# SD_Node.net
KiCad netlist of a schematic drawn in EAGLE
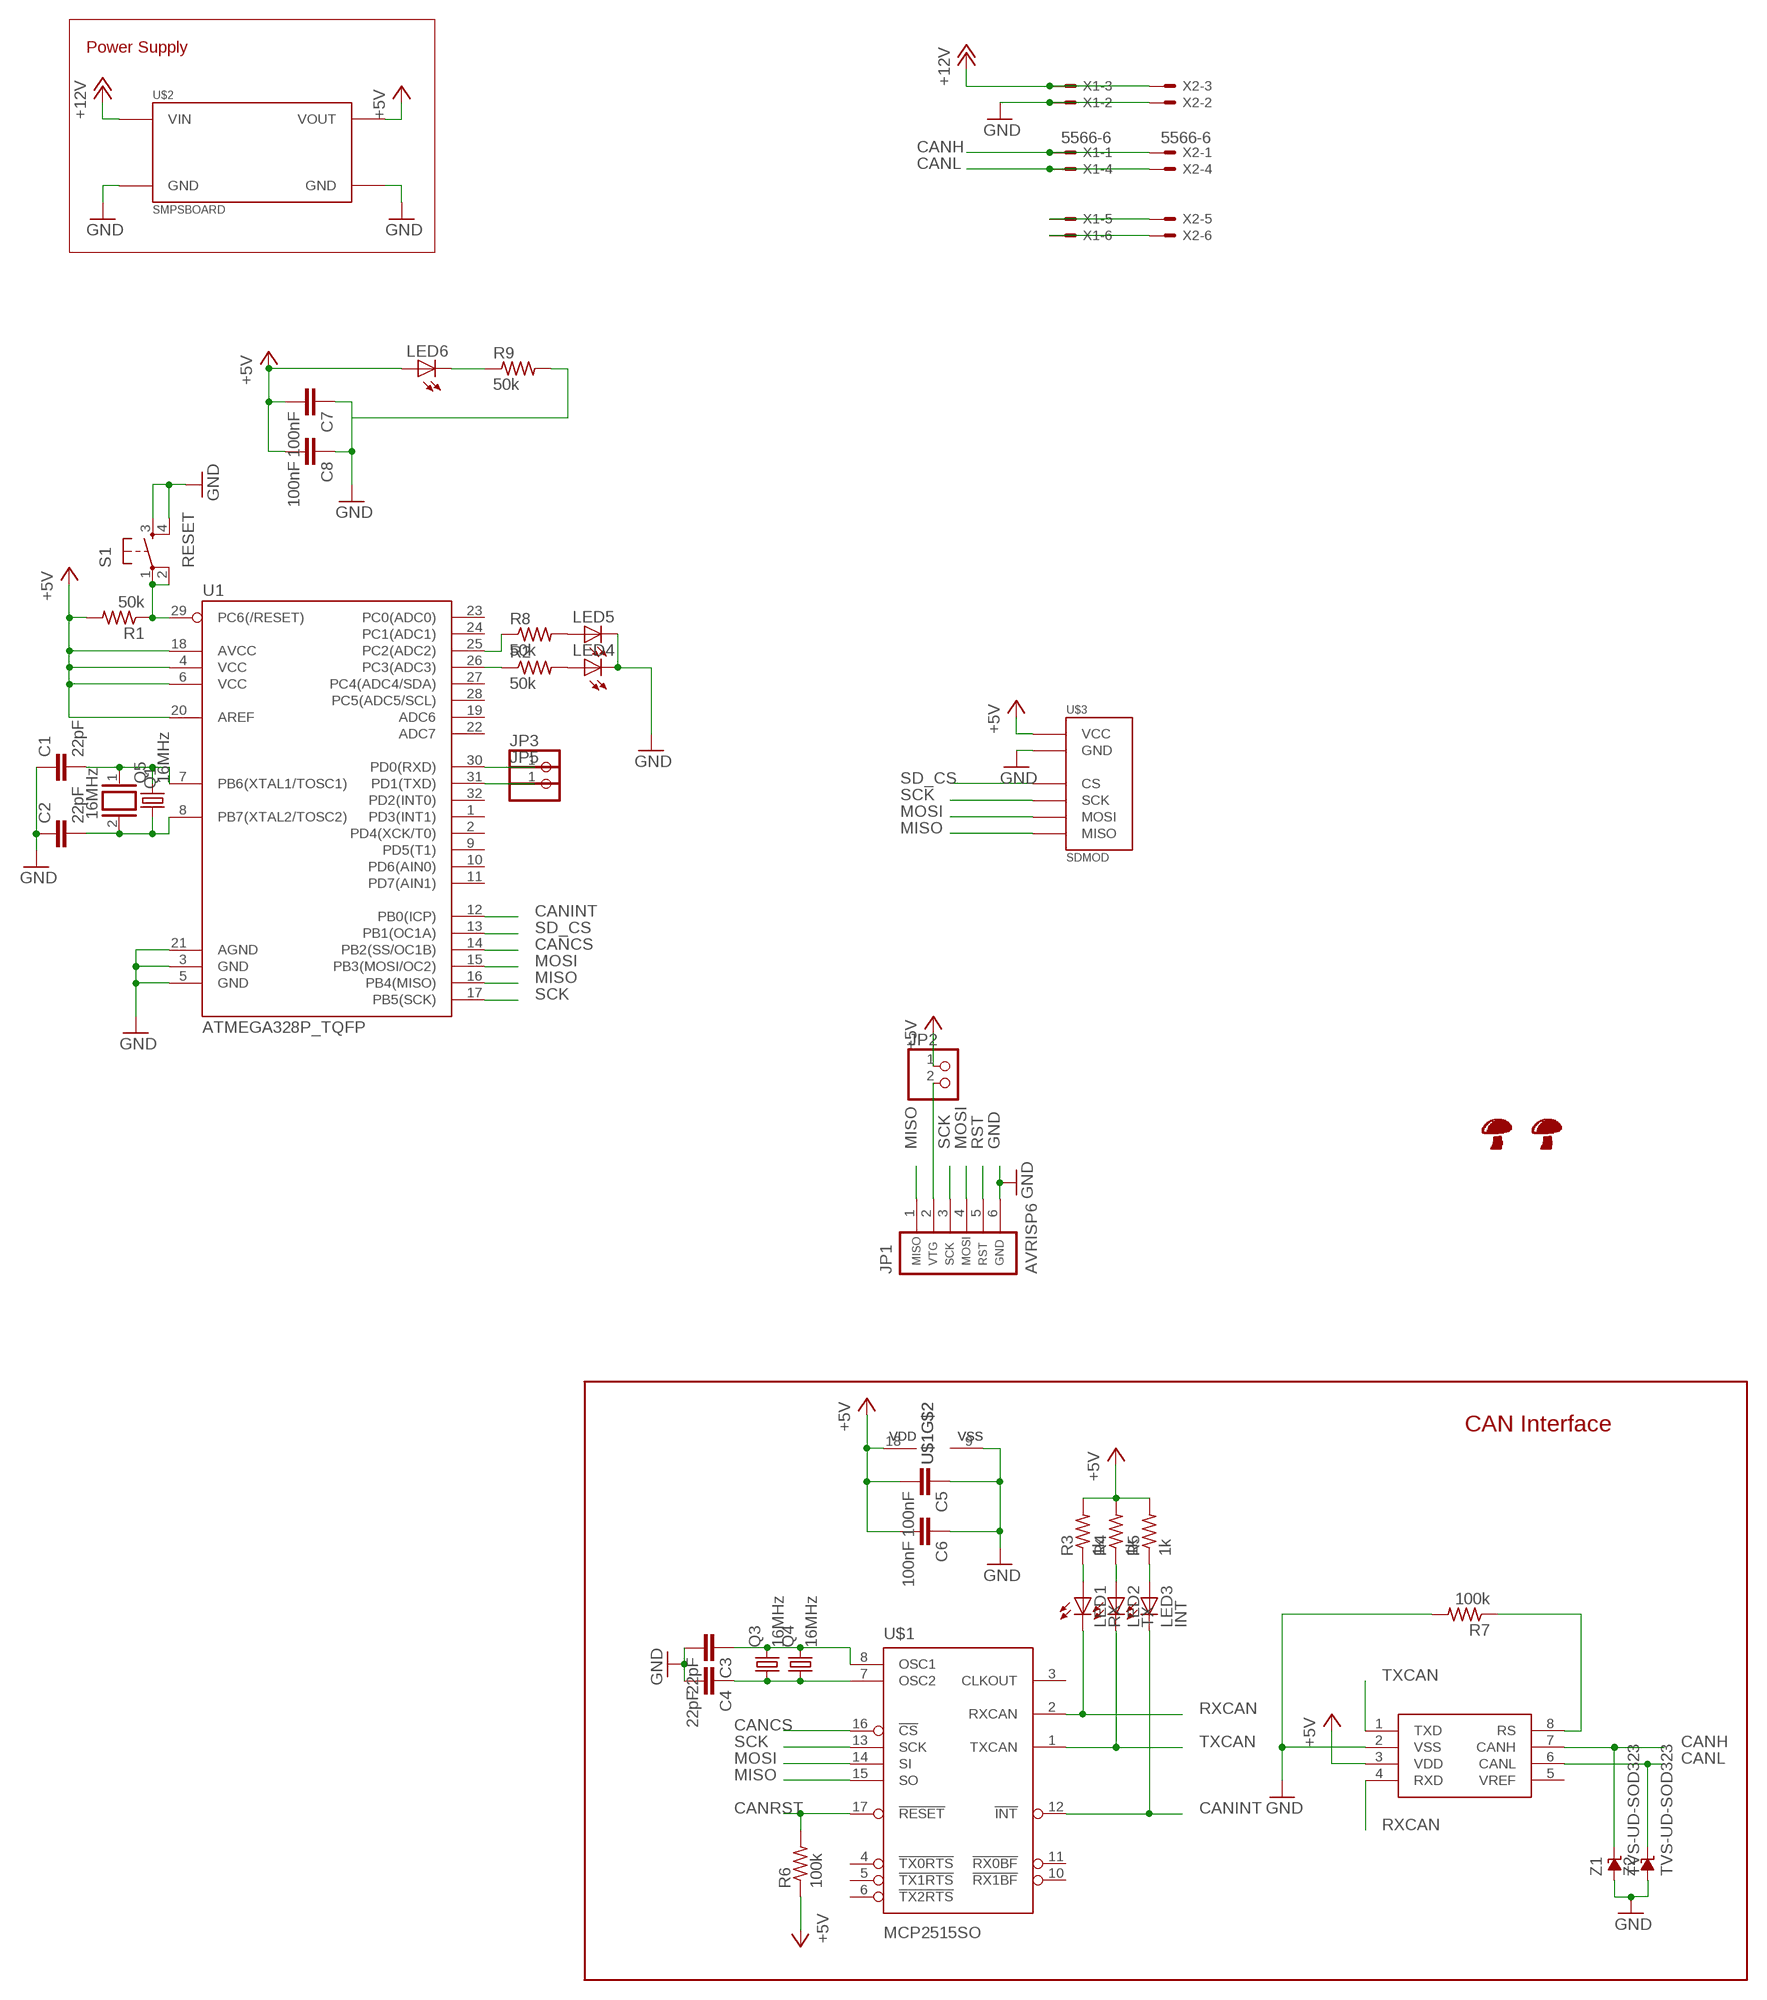
[diagram p0: schematic, sheet 1]

(export (version "E")
  (design (tool "Eeschema 10.0.6"))
  (components
    (comp (ref "C1")
      (value "22pF")
      (footprint "eagle-import:C0805")
      (libsource (lib "eagle-import") (part "C-EUC0805"))
    )
    (comp (ref "C2")
      (value "22pF")
      (footprint "eagle-import:C0805")
      (libsource (lib "eagle-import") (part "C-EUC0805"))
    )
    (comp (ref "C3")
      (value "22pF")
      (footprint "eagle-import:C0805K")
      (libsource (lib "eagle-import") (part "C-EUC0805K"))
    )
    (comp (ref "C4")
      (value "22pF")
      (footprint "eagle-import:C0805K")
      (libsource (lib "eagle-import") (part "C-EUC0805K"))
    )
    (comp (ref "C5")
      (value "100nF")
      (footprint "eagle-import:C0805K")
      (libsource (lib "eagle-import") (part "C-EUC0805K"))
    )
    (comp (ref "C6")
      (value "100nF")
      (footprint "eagle-import:C0805K")
      (libsource (lib "eagle-import") (part "C-EUC0805K"))
    )
    (comp (ref "C7")
      (value "100nF")
      (footprint "eagle-import:C0805")
      (libsource (lib "eagle-import") (part "C-EUC0805"))
    )
    (comp (ref "C8")
      (value "100nF")
      (footprint "eagle-import:C0805")
      (libsource (lib "eagle-import") (part "C-EUC0805"))
    )
    (comp (ref "JP1")
      (value "AVRISP6")
      (footprint "eagle-import:HDR-75869-131")
      (libsource (lib "eagle-import") (part "AVR-ISP6-75869-131"))
    )
    (comp (ref "JP2")
      (value "PINHD-1X2")
      (footprint "eagle-import:1X02")
      (libsource (lib "eagle-import") (part "PINHD-1X2"))
    )
    (comp (ref "JP3")
      (value "PINHD-1X1")
      (footprint "eagle-import:1X01")
      (libsource (lib "eagle-import") (part "PINHD-1X1"))
    )
    (comp (ref "JP5")
      (value "PINHD-1X1")
      (footprint "eagle-import:1X01")
      (libsource (lib "eagle-import") (part "PINHD-1X1"))
    )
    (comp (ref "LED1")
      (value "RX")
      (footprint "eagle-import:CHIP-LED0805")
      (libsource (lib "eagle-import") (part "LEDCHIP-LED0805"))
    )
    (comp (ref "LED2")
      (value "TX")
      (footprint "eagle-import:CHIP-LED0805")
      (libsource (lib "eagle-import") (part "LEDCHIP-LED0805"))
    )
    (comp (ref "LED3")
      (value "INT")
      (footprint "eagle-import:CHIP-LED0805")
      (libsource (lib "eagle-import") (part "LEDCHIP-LED0805"))
    )
    (comp (ref "LED4")
      (value "LEDCHIP-LED0805")
      (footprint "eagle-import:CHIP-LED0805")
      (libsource (lib "eagle-import") (part "LEDCHIP-LED0805"))
    )
    (comp (ref "LED5")
      (value "LEDCHIP-LED0805")
      (footprint "eagle-import:CHIP-LED0805")
      (libsource (lib "eagle-import") (part "LEDCHIP-LED0805"))
    )
    (comp (ref "LED6")
      (value "LEDCHIP-LED0805")
      (footprint "eagle-import:CHIP-LED0805")
      (libsource (lib "eagle-import") (part "LEDCHIP-LED0805"))
    )
    (comp (ref "Q1")
      (value "16MHz")
      (footprint "eagle-import:QS")
      (libsource (lib "eagle-import") (part "XTAL/S"))
    )
    (comp (ref "Q3")
      (value "16MHz")
      (footprint "eagle-import:HC49_S")
      (libsource (lib "eagle-import") (part "CRYSTALHC49S"))
    )
    (comp (ref "Q4")
      (value "16MHz")
      (footprint "eagle-import:HC49UP")
      (libsource (lib "eagle-import") (part "CRYSTALHC49UP"))
    )
    (comp (ref "Q5")
      (value "16MHz")
      (footprint "eagle-import:HC49UP")
      (libsource (lib "eagle-import") (part "CRYSTALHC49UP"))
    )
    (comp (ref "R1")
      (value "50k")
      (footprint "eagle-import:R0805")
      (libsource (lib "eagle-import") (part "R-US_R0805"))
    )
    (comp (ref "R2")
      (value "50k")
      (footprint "eagle-import:R0805")
      (libsource (lib "eagle-import") (part "R-US_R0805"))
    )
    (comp (ref "R3")
      (value "1k")
      (footprint "eagle-import:R0805")
      (libsource (lib "eagle-import") (part "R-US_R0805"))
    )
    (comp (ref "R4")
      (value "1k")
      (footprint "eagle-import:R0805")
      (libsource (lib "eagle-import") (part "R-US_R0805"))
    )
    (comp (ref "R5")
      (value "1k")
      (footprint "eagle-import:R0805")
      (libsource (lib "eagle-import") (part "R-US_R0805"))
    )
    (comp (ref "R6")
      (value "100k")
      (footprint "eagle-import:R0805")
      (libsource (lib "eagle-import") (part "R-US_R0805"))
    )
    (comp (ref "R7")
      (value "100k")
      (footprint "eagle-import:R0805")
      (libsource (lib "eagle-import") (part "R-US_R0805"))
    )
    (comp (ref "R8")
      (value "50k")
      (footprint "eagle-import:R0805")
      (libsource (lib "eagle-import") (part "R-US_R0805"))
    )
    (comp (ref "R9")
      (value "50k")
      (footprint "eagle-import:R0805")
      (libsource (lib "eagle-import") (part "R-US_R0805"))
    )
    (comp (ref "S1")
      (value "RESET")
      (footprint "eagle-import:TACTILE_SWITCH_SMD")
      (libsource (lib "eagle-import") (part "TAC_SWITCHSMD"))
    )
    (comp (ref "U$1")
      (value "MCP2515SO")
      (footprint "eagle-import:SO-18W")
      (libsource (lib "eagle-import") (part "MCP2515SO"))
    )
    (comp (ref "U$2")
      (value "SMPSBOARD")
      (footprint "eagle-import:SMPSBOARD")
      (libsource (lib "eagle-import") (part "SMPSBOARD"))
    )
    (comp (ref "U$3")
      (value "SDMOD")
      (footprint "eagle-import:SDMOD")
      (libsource (lib "eagle-import") (part "SDMOD"))
    )
    (comp (ref "U$4")
      (value "SHROOM15MM")
      (footprint "eagle-import:SHROOM15MM")
      (libsource (lib "eagle-import") (part "SHROOM15MM"))
    )
    (comp (ref "U$5")
      (value "SHROOM5MM")
      (footprint "eagle-import:SHROOM")
      (libsource (lib "eagle-import") (part "SHROOM5MM"))
    )
    (comp (ref "U1")
      (value "ATMEGA328P_TQFP")
      (footprint "eagle-import:TQFP32-08")
      (libsource (lib "eagle-import") (part "ATMEGA328P_TQFP"))
    )
    (comp (ref "U2")
      (value "MCP2551")
      (footprint "eagle-import:SO08")
      (libsource (lib "eagle-import") (part "MCP2551"))
    )
    (comp (ref "X1")
      (value "5566-6")
      (footprint "eagle-import:5566-6")
      (fields (field (name "MPN") "95566-61002"))
      (libsource (lib "eagle-import") (part "5566-6"))
    )
    (comp (ref "X2")
      (value "5566-6")
      (footprint "eagle-import:5566-6")
      (fields (field (name "MPN") "95566-61002"))
      (libsource (lib "eagle-import") (part "5566-6"))
    )
    (comp (ref "Z1")
      (value "TVS-UD-SOD323")
      (footprint "eagle-import:SOD323")
      (libsource (lib "eagle-import") (part "TVS-UD-SOD323"))
    )
    (comp (ref "Z2")
      (value "TVS-UD-SOD323")
      (footprint "eagle-import:SOD323")
      (libsource (lib "eagle-import") (part "TVS-UD-SOD323"))
    )
  )
  (nets
    (net (code "1") (name "+5V") (class "Default")
      (node (ref "C5") (pin "2") (pinfunction "2_2") (pintype "passive"))
      (node (ref "C6") (pin "2") (pinfunction "2_2") (pintype "passive"))
      (node (ref "C7") (pin "2") (pinfunction "2_2") (pintype "passive"))
      (node (ref "C8") (pin "2") (pinfunction "2_2") (pintype "passive"))
      (node (ref "JP2") (pin "1") (pinfunction "1_1") (pintype "passive"))
      (node (ref "LED6") (pin "A") (pinfunction "A_A") (pintype "passive"))
      (node (ref "R1") (pin "2") (pinfunction "2_2") (pintype "passive"))
      (node (ref "R3") (pin "2") (pinfunction "2_2") (pintype "passive"))
      (node (ref "R4") (pin "2") (pinfunction "2_2") (pintype "passive"))
      (node (ref "R5") (pin "2") (pinfunction "2_2") (pintype "passive"))
      (node (ref "R6") (pin "1") (pinfunction "1_1") (pintype "passive"))
      (node (ref "U$1") (pin "18") (pinfunction "VDD_18") (pintype "power_in"))
      (node (ref "U$2") (pin "VOUT") (pinfunction "VOUT_VOUT") (pintype "bidirectional"))
      (node (ref "U$3") (pin "VCC") (pinfunction "VCC_VCC") (pintype "bidirectional"))
      (node (ref "U1") (pin "18") (pinfunction "AVCC_18") (pintype "bidirectional"))
      (node (ref "U1") (pin "20") (pinfunction "AREF_20") (pintype "bidirectional"))
      (node (ref "U1") (pin "4") (pinfunction "VCC_4") (pintype "bidirectional"))
      (node (ref "U1") (pin "6") (pinfunction "VCC_6") (pintype "bidirectional"))
      (node (ref "U2") (pin "3") (pinfunction "VDD_3") (pintype "bidirectional"))
    )
    (net (code "2") (name "+12V") (class "Default")
      (node (ref "U$2") (pin "VIN") (pinfunction "VIN_VIN") (pintype "bidirectional"))
      (node (ref "X1") (pin "3") (pinfunction "S_3") (pintype "passive"))
      (node (ref "X2") (pin "3") (pinfunction "S_3") (pintype "passive"))
    )
    (net (code "3") (name "/CANCS") (class "Default")
      (node (ref "U$1") (pin "16") (pinfunction "~{CS}_16") (pintype "input"))
      (node (ref "U1") (pin "14") (pinfunction "PB2(SS/OC1B)_14") (pintype "bidirectional"))
    )
    (net (code "4") (name "/CANH") (class "Default")
      (node (ref "U2") (pin "7") (pinfunction "CANH_7") (pintype "bidirectional"))
      (node (ref "X1") (pin "1") (pinfunction "S_1") (pintype "passive"))
      (node (ref "X2") (pin "1") (pinfunction "S_1") (pintype "passive"))
      (node (ref "Z1") (pin "C") (pinfunction "C_C") (pintype "passive"))
    )
    (net (code "5") (name "/CANINT") (class "Default")
      (node (ref "LED3") (pin "C") (pinfunction "C_C") (pintype "passive"))
      (node (ref "U$1") (pin "12") (pinfunction "~{INT}_12") (pintype "output"))
      (node (ref "U1") (pin "12") (pinfunction "PB0(ICP)_12") (pintype "bidirectional"))
    )
    (net (code "6") (name "/CANL") (class "Default")
      (node (ref "U2") (pin "6") (pinfunction "CANL_6") (pintype "bidirectional"))
      (node (ref "X1") (pin "4") (pinfunction "S_4") (pintype "passive"))
      (node (ref "X2") (pin "4") (pinfunction "S_4") (pintype "passive"))
      (node (ref "Z2") (pin "C") (pinfunction "C_C") (pintype "passive"))
    )
    (net (code "7") (name "/CANRST") (class "Default")
      (node (ref "R6") (pin "2") (pinfunction "2_2") (pintype "passive"))
      (node (ref "U$1") (pin "17") (pinfunction "~{RESET}_17") (pintype "input"))
    )
    (net (code "8") (name "/MISO") (class "Default")
      (node (ref "JP1") (pin "1") (pinfunction "1_1") (pintype "passive"))
      (node (ref "U$1") (pin "15") (pinfunction "SO_15") (pintype "output"))
      (node (ref "U$3") (pin "MISO") (pinfunction "MISO_MISO") (pintype "bidirectional"))
      (node (ref "U1") (pin "16") (pinfunction "PB4(MISO)_16") (pintype "bidirectional"))
    )
    (net (code "9") (name "/MOSI") (class "Default")
      (node (ref "JP1") (pin "4") (pinfunction "4_4") (pintype "passive"))
      (node (ref "U$1") (pin "14") (pinfunction "SI_14") (pintype "input"))
      (node (ref "U$3") (pin "MOSI") (pinfunction "MOSI_MOSI") (pintype "bidirectional"))
      (node (ref "U1") (pin "15") (pinfunction "PB3(MOSI/OC2)_15") (pintype "bidirectional"))
    )
    (net (code "10") (name "/RST") (class "Default")
      (node (ref "JP1") (pin "5") (pinfunction "5_5") (pintype "passive"))
      (node (ref "R1") (pin "1") (pinfunction "1_1") (pintype "passive"))
      (node (ref "S1") (pin "1") (pinfunction "1_1") (pintype "passive"))
      (node (ref "S1") (pin "2") (pinfunction "2_2") (pintype "passive"))
      (node (ref "U1") (pin "29") (pinfunction "PC6(/RESET)_29") (pintype "bidirectional"))
    )
    (net (code "11") (name "/RXCAN") (class "Default")
      (node (ref "LED1") (pin "C") (pinfunction "C_C") (pintype "passive"))
      (node (ref "U$1") (pin "2") (pinfunction "RXCAN_2") (pintype "input"))
      (node (ref "U2") (pin "4") (pinfunction "RXD_4") (pintype "bidirectional"))
    )
    (net (code "12") (name "/SCK") (class "Default")
      (node (ref "JP1") (pin "3") (pinfunction "3_3") (pintype "passive"))
      (node (ref "U$1") (pin "13") (pinfunction "SCK_13") (pintype "input"))
      (node (ref "U$3") (pin "SCK") (pinfunction "SCK_SCK") (pintype "bidirectional"))
      (node (ref "U1") (pin "17") (pinfunction "PB5(SCK)_17") (pintype "bidirectional"))
    )
    (net (code "13") (name "/SD_CS") (class "Default")
      (node (ref "U$3") (pin "CS") (pinfunction "CS_CS") (pintype "bidirectional"))
      (node (ref "U1") (pin "13") (pinfunction "PB1(OC1A)_13") (pintype "bidirectional"))
    )
    (net (code "14") (name "/TXCAN") (class "Default")
      (node (ref "LED2") (pin "C") (pinfunction "C_C") (pintype "passive"))
      (node (ref "U$1") (pin "1") (pinfunction "TXCAN_1") (pintype "output"))
      (node (ref "U2") (pin "1") (pinfunction "TXD_1") (pintype "bidirectional"))
    )
    (net (code "15") (name "GND") (class "Default")
      (node (ref "C1") (pin "1") (pinfunction "1_1") (pintype "passive"))
      (node (ref "C2") (pin "1") (pinfunction "1_1") (pintype "passive"))
      (node (ref "C3") (pin "2") (pinfunction "2_2") (pintype "passive"))
      (node (ref "C4") (pin "2") (pinfunction "2_2") (pintype "passive"))
      (node (ref "C5") (pin "1") (pinfunction "1_1") (pintype "passive"))
      (node (ref "C6") (pin "1") (pinfunction "1_1") (pintype "passive"))
      (node (ref "C7") (pin "1") (pinfunction "1_1") (pintype "passive"))
      (node (ref "C8") (pin "1") (pinfunction "1_1") (pintype "passive"))
      (node (ref "JP1") (pin "6") (pinfunction "6_6") (pintype "passive"))
      (node (ref "LED4") (pin "C") (pinfunction "C_C") (pintype "passive"))
      (node (ref "LED5") (pin "C") (pinfunction "C_C") (pintype "passive"))
      (node (ref "R7") (pin "2") (pinfunction "2_2") (pintype "passive"))
      (node (ref "R9") (pin "2") (pinfunction "2_2") (pintype "passive"))
      (node (ref "S1") (pin "3") (pinfunction "3_3") (pintype "passive"))
      (node (ref "S1") (pin "4") (pinfunction "4_4") (pintype "passive"))
      (node (ref "U$1") (pin "9") (pinfunction "VSS_9") (pintype "power_in"))
      (node (ref "U$2") (pin "GND") (pinfunction "GND_GND") (pintype "bidirectional"))
      (node (ref "U$2") (pin "GND@") (pinfunction "GND_GND@") (pintype "bidirectional"))
      (node (ref "U$3") (pin "GND") (pinfunction "GND_GND") (pintype "bidirectional"))
      (node (ref "U1") (pin "21") (pinfunction "AGND_21") (pintype "bidirectional"))
      (node (ref "U1") (pin "3") (pinfunction "GND_3") (pintype "bidirectional"))
      (node (ref "U1") (pin "5") (pinfunction "GND_5") (pintype "bidirectional"))
      (node (ref "U2") (pin "2") (pinfunction "VSS_2") (pintype "bidirectional"))
      (node (ref "X1") (pin "2") (pinfunction "S_2") (pintype "passive"))
      (node (ref "X2") (pin "2") (pinfunction "S_2") (pintype "passive"))
      (node (ref "Z1") (pin "A") (pinfunction "A_A") (pintype "passive"))
      (node (ref "Z2") (pin "A") (pinfunction "A_A") (pintype "passive"))
    )
    (net (code "16") (name "Net-(JP1-Pad2)") (class "Default")
      (node (ref "JP1") (pin "2") (pinfunction "2_2") (pintype "passive"))
      (node (ref "JP2") (pin "2") (pinfunction "2_2") (pintype "passive"))
    )
    (net (code "17") (name "Net-(LED1-PadA)") (class "Default")
      (node (ref "LED1") (pin "A") (pinfunction "A_A") (pintype "passive"))
      (node (ref "R3") (pin "1") (pinfunction "1_1") (pintype "passive"))
    )
    (net (code "18") (name "Net-(LED2-PadA)") (class "Default")
      (node (ref "LED2") (pin "A") (pinfunction "A_A") (pintype "passive"))
      (node (ref "R4") (pin "1") (pinfunction "1_1") (pintype "passive"))
    )
    (net (code "19") (name "Net-(LED3-PadA)") (class "Default")
      (node (ref "LED3") (pin "A") (pinfunction "A_A") (pintype "passive"))
      (node (ref "R5") (pin "1") (pinfunction "1_1") (pintype "passive"))
    )
    (net (code "20") (name "Net-(LED4-PadA)") (class "Default")
      (node (ref "LED4") (pin "A") (pinfunction "A_A") (pintype "passive"))
      (node (ref "R2") (pin "2") (pinfunction "2_2") (pintype "passive"))
    )
    (net (code "21") (name "Net-(LED5-PadA)") (class "Default")
      (node (ref "LED5") (pin "A") (pinfunction "A_A") (pintype "passive"))
      (node (ref "R8") (pin "2") (pinfunction "2_2") (pintype "passive"))
    )
    (net (code "22") (name "Net-(LED6-PadC)") (class "Default")
      (node (ref "LED6") (pin "C") (pinfunction "C_C") (pintype "passive"))
      (node (ref "R9") (pin "1") (pinfunction "1_1") (pintype "passive"))
    )
    (net (code "23") (name "Net-(U$1A-OSC1)") (class "Default")
      (node (ref "C3") (pin "1") (pinfunction "1_1") (pintype "passive"))
      (node (ref "Q3") (pin "2") (pinfunction "2_2") (pintype "passive"))
      (node (ref "Q4") (pin "2") (pinfunction "2_2") (pintype "passive"))
      (node (ref "U$1") (pin "8") (pinfunction "OSC1_8") (pintype "input"))
    )
    (net (code "24") (name "Net-(U$1A-OSC2)") (class "Default")
      (node (ref "C4") (pin "1") (pinfunction "1_1") (pintype "passive"))
      (node (ref "Q3") (pin "1") (pinfunction "1_1") (pintype "passive"))
      (node (ref "Q4") (pin "1") (pinfunction "1_1") (pintype "passive"))
      (node (ref "U$1") (pin "7") (pinfunction "OSC2_7") (pintype "output"))
    )
    (net (code "25") (name "Net-(U1-PB6(XTAL1{slash}TOSC1))") (class "Default")
      (node (ref "C1") (pin "2") (pinfunction "2_2") (pintype "passive"))
      (node (ref "Q1") (pin "1") (pinfunction "1_1") (pintype "passive"))
      (node (ref "Q5") (pin "2") (pinfunction "2_2") (pintype "passive"))
      (node (ref "U1") (pin "7") (pinfunction "PB6(XTAL1/TOSC1)_7") (pintype "bidirectional"))
    )
    (net (code "26") (name "Net-(U1-PB7(XTAL2{slash}TOSC2))") (class "Default")
      (node (ref "C2") (pin "2") (pinfunction "2_2") (pintype "passive"))
      (node (ref "Q1") (pin "2") (pinfunction "2_2") (pintype "passive"))
      (node (ref "Q5") (pin "1") (pinfunction "1_1") (pintype "passive"))
      (node (ref "U1") (pin "8") (pinfunction "PB7(XTAL2/TOSC2)_8") (pintype "bidirectional"))
    )
    (net (code "27") (name "Net-(U1-PC2(ADC2))") (class "Default")
      (node (ref "R8") (pin "1") (pinfunction "1_1") (pintype "passive"))
      (node (ref "U1") (pin "25") (pinfunction "PC2(ADC2)_25") (pintype "bidirectional"))
    )
    (net (code "28") (name "Net-(U1-PC3(ADC3))") (class "Default")
      (node (ref "R2") (pin "1") (pinfunction "1_1") (pintype "passive"))
      (node (ref "U1") (pin "26") (pinfunction "PC3(ADC3)_26") (pintype "bidirectional"))
    )
    (net (code "29") (name "Net-(U1-PD0(RXD))") (class "Default")
      (node (ref "JP3") (pin "1") (pinfunction "1_1") (pintype "passive"))
      (node (ref "U1") (pin "30") (pinfunction "PD0(RXD)_30") (pintype "bidirectional"))
    )
    (net (code "30") (name "Net-(U1-PD1(TXD))") (class "Default")
      (node (ref "JP5") (pin "1") (pinfunction "1_1") (pintype "passive"))
      (node (ref "U1") (pin "31") (pinfunction "PD1(TXD)_31") (pintype "bidirectional"))
    )
    (net (code "31") (name "Net-(U2-RS)") (class "Default")
      (node (ref "R7") (pin "1") (pinfunction "1_1") (pintype "passive"))
      (node (ref "U2") (pin "8") (pinfunction "RS_8") (pintype "bidirectional"))
    )
    (net (code "32") (name "Net-(X1E-S)") (class "Default")
      (node (ref "X1") (pin "5") (pinfunction "S_5") (pintype "passive"))
      (node (ref "X2") (pin "5") (pinfunction "S_5") (pintype "passive"))
    )
    (net (code "33") (name "Net-(X1F-S)") (class "Default")
      (node (ref "X1") (pin "6") (pinfunction "S_6") (pintype "passive"))
      (node (ref "X2") (pin "6") (pinfunction "S_6") (pintype "passive"))
    )
    (net (code "34") (name "unconnected-(U$1A-CLKOUT-Pad3)") (class "Default")
      (node (ref "U$1") (pin "3") (pinfunction "CLKOUT_3") (pintype "output"))
    )
    (net (code "35") (name "unconnected-(U$1A-~{RX0BF}-Pad11)") (class "Default")
      (node (ref "U$1") (pin "11") (pinfunction "~{RX0BF}_11") (pintype "output"))
    )
    (net (code "36") (name "unconnected-(U$1A-~{RX1BF}-Pad10)") (class "Default")
      (node (ref "U$1") (pin "10") (pinfunction "~{RX1BF}_10") (pintype "output"))
    )
    (net (code "37") (name "unconnected-(U$1A-~{TX0RTS}-Pad4)") (class "Default")
      (node (ref "U$1") (pin "4") (pinfunction "~{TX0RTS}_4") (pintype "input"))
    )
    (net (code "38") (name "unconnected-(U$1A-~{TX1RTS}-Pad5)") (class "Default")
      (node (ref "U$1") (pin "5") (pinfunction "~{TX1RTS}_5") (pintype "input"))
    )
    (net (code "39") (name "unconnected-(U$1A-~{TX2RTS}-Pad6)") (class "Default")
      (node (ref "U$1") (pin "6") (pinfunction "~{TX2RTS}_6") (pintype "input"))
    )
    (net (code "40") (name "unconnected-(U1-ADC6-Pad19)") (class "Default")
      (node (ref "U1") (pin "19") (pinfunction "ADC6_19") (pintype "bidirectional"))
    )
    (net (code "41") (name "unconnected-(U1-ADC7-Pad22)") (class "Default")
      (node (ref "U1") (pin "22") (pinfunction "ADC7_22") (pintype "bidirectional"))
    )
    (net (code "42") (name "unconnected-(U1-PC0(ADC0)-Pad23)") (class "Default")
      (node (ref "U1") (pin "23") (pinfunction "PC0(ADC0)_23") (pintype "bidirectional"))
    )
    (net (code "43") (name "unconnected-(U1-PC1(ADC1)-Pad24)") (class "Default")
      (node (ref "U1") (pin "24") (pinfunction "PC1(ADC1)_24") (pintype "bidirectional"))
    )
    (net (code "44") (name "unconnected-(U1-PC4(ADC4{slash}SDA)-Pad27)") (class "Default")
      (node (ref "U1") (pin "27") (pinfunction "PC4(ADC4/SDA)_27") (pintype "bidirectional"))
    )
    (net (code "45") (name "unconnected-(U1-PC5(ADC5{slash}SCL)-Pad28)") (class "Default")
      (node (ref "U1") (pin "28") (pinfunction "PC5(ADC5/SCL)_28") (pintype "bidirectional"))
    )
    (net (code "46") (name "unconnected-(U1-PD2(INT0)-Pad32)") (class "Default")
      (node (ref "U1") (pin "32") (pinfunction "PD2(INT0)_32") (pintype "bidirectional"))
    )
    (net (code "47") (name "unconnected-(U1-PD3(INT1)-Pad1)") (class "Default")
      (node (ref "U1") (pin "1") (pinfunction "PD3(INT1)_1") (pintype "bidirectional"))
    )
    (net (code "48") (name "unconnected-(U1-PD4(XCK{slash}T0)-Pad2)") (class "Default")
      (node (ref "U1") (pin "2") (pinfunction "PD4(XCK/T0)_2") (pintype "bidirectional"))
    )
    (net (code "49") (name "unconnected-(U1-PD5(T1)-Pad9)") (class "Default")
      (node (ref "U1") (pin "9") (pinfunction "PD5(T1)_9") (pintype "bidirectional"))
    )
    (net (code "50") (name "unconnected-(U1-PD6(AIN0)-Pad10)") (class "Default")
      (node (ref "U1") (pin "10") (pinfunction "PD6(AIN0)_10") (pintype "bidirectional"))
    )
    (net (code "51") (name "unconnected-(U1-PD7(AIN1)-Pad11)") (class "Default")
      (node (ref "U1") (pin "11") (pinfunction "PD7(AIN1)_11") (pintype "bidirectional"))
    )
    (net (code "52") (name "unconnected-(U2-VREF-Pad5)") (class "Default")
      (node (ref "U2") (pin "5") (pinfunction "VREF_5") (pintype "bidirectional"))
    )
  )
)
